# OPA4377__V2_0.net
KiCad netlist of a schematic drawn in EasyEDA Pro
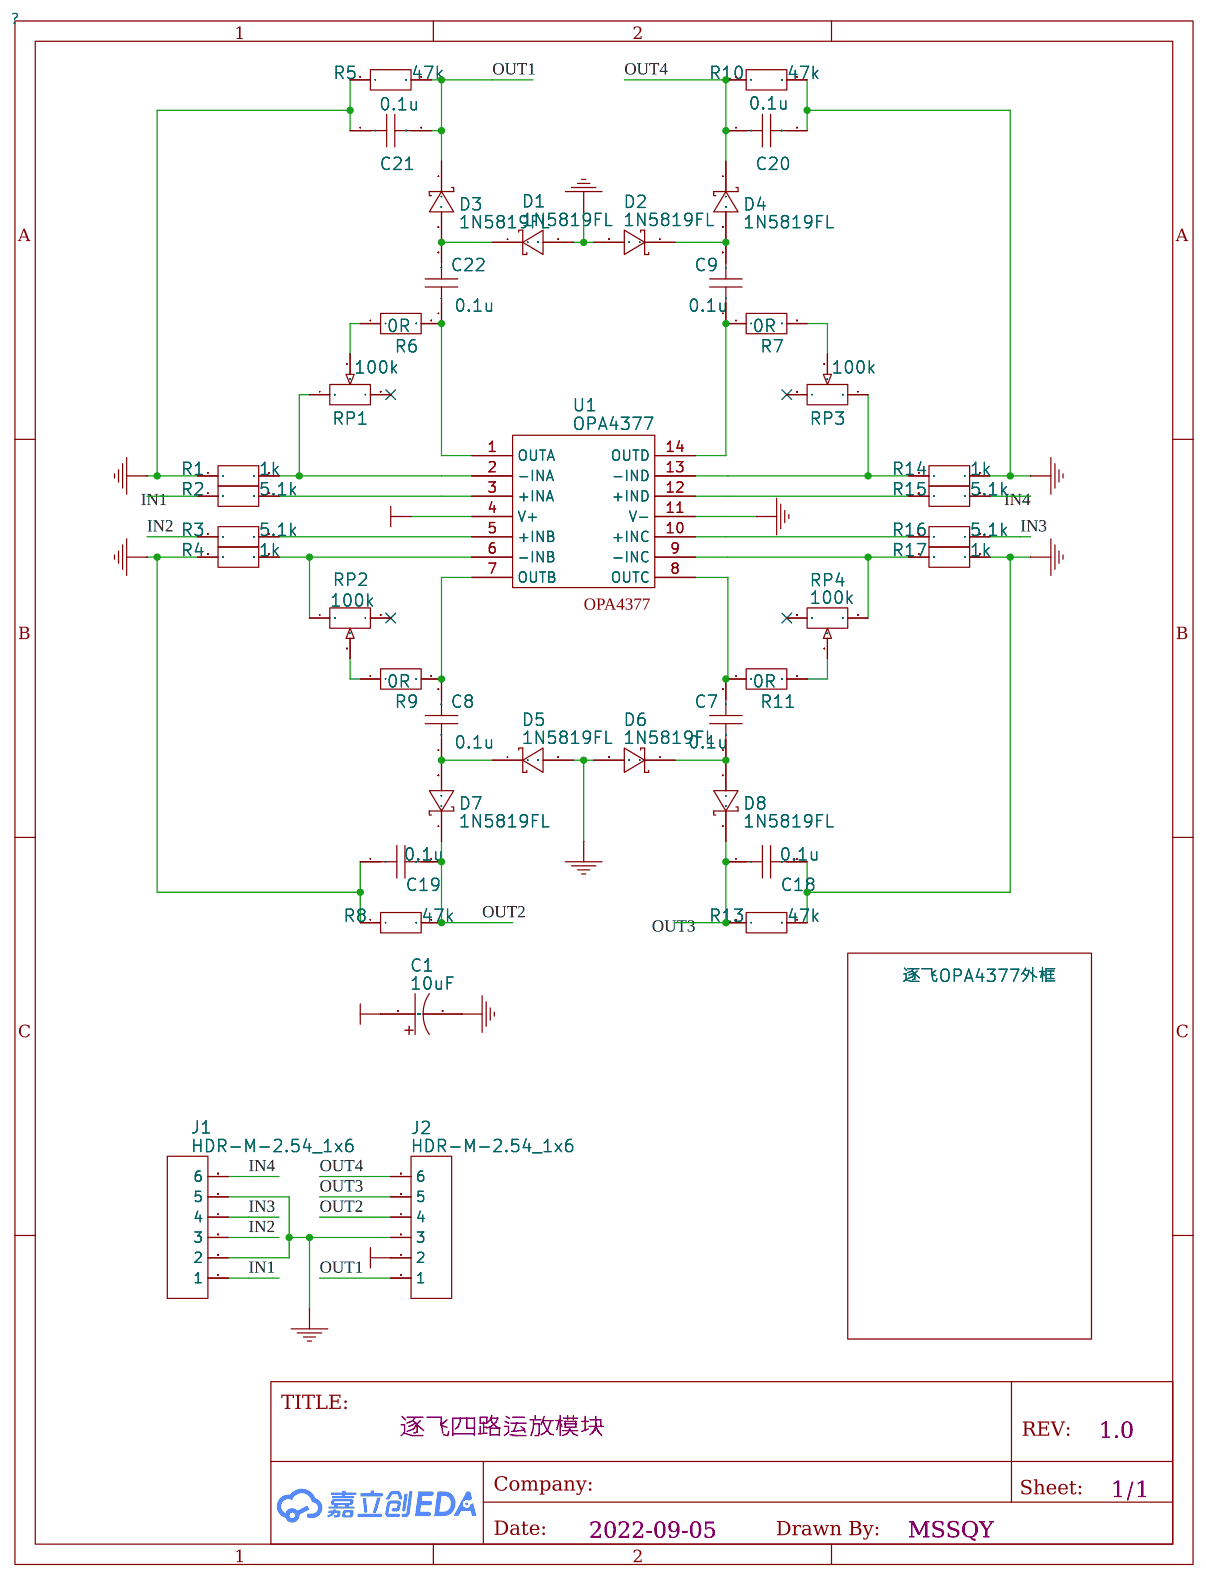
[diagram p0: schematic sheet]

(export (version "E")
  (design (tool "Eeschema 10.0.6"))
  (components
    (comp (ref "C1")
      (value "10uF")
      (fields (field (name "Manufacturer Part") "CA45-A-10V-10μF-K") (field (name "Manufacturer") "TORCH"))
      (libsource (lib "easyedapro") (part "10uF"))
    )
    (comp (ref "C7")
      (value "0.1u")
      (fields (field (name "Manufacturer Part") "MT18N101J500CT") (field (name "Manufacturer") "Huaxin S&T"))
      (libsource (lib "easyedapro") (part "0.1u"))
    )
    (comp (ref "C8")
      (value "0.1u")
      (fields (field (name "Manufacturer Part") "MT18N101J500CT") (field (name "Manufacturer") "Huaxin S&T"))
      (libsource (lib "easyedapro") (part "0.1u"))
    )
    (comp (ref "C9")
      (value "0.1u")
      (fields (field (name "Manufacturer Part") "MT18N101J500CT") (field (name "Manufacturer") "Huaxin S&T"))
      (libsource (lib "easyedapro") (part "0.1u"))
    )
    (comp (ref "C18")
      (value "0.1u")
      (fields (field (name "Manufacturer Part") "MT18N101J500CT") (field (name "Manufacturer") "Huaxin S&T"))
      (libsource (lib "easyedapro") (part "0.1u"))
    )
    (comp (ref "C19")
      (value "0.1u")
      (fields (field (name "Manufacturer Part") "MT18N101J500CT") (field (name "Manufacturer") "Huaxin S&T"))
      (libsource (lib "easyedapro") (part "0.1u"))
    )
    (comp (ref "C20")
      (value "0.1u")
      (fields (field (name "Manufacturer Part") "MT18N101J500CT") (field (name "Manufacturer") "Huaxin S&T"))
      (libsource (lib "easyedapro") (part "0.1u"))
    )
    (comp (ref "C21")
      (value "0.1u")
      (fields (field (name "Manufacturer Part") "MT18N101J500CT") (field (name "Manufacturer") "Huaxin S&T"))
      (libsource (lib "easyedapro") (part "0.1u"))
    )
    (comp (ref "C22")
      (value "0.1u")
      (fields (field (name "Manufacturer Part") "MT18N101J500CT") (field (name "Manufacturer") "Huaxin S&T"))
      (libsource (lib "easyedapro") (part "0.1u"))
    )
    (comp (ref "D1")
      (value "1N5819FL")
      (fields (field (name "Manufacturer") "KEXIN"))
      (libsource (lib "easyedapro") (part "1N5819FL"))
    )
    (comp (ref "D2")
      (value "1N5819FL")
      (fields (field (name "Manufacturer") "KEXIN"))
      (libsource (lib "easyedapro") (part "1N5819FL"))
    )
    (comp (ref "D3")
      (value "1N5819FL")
      (fields (field (name "Manufacturer") "KEXIN"))
      (libsource (lib "easyedapro") (part "1N5819FL"))
    )
    (comp (ref "D4")
      (value "1N5819FL")
      (fields (field (name "Manufacturer") "KEXIN"))
      (libsource (lib "easyedapro") (part "1N5819FL"))
    )
    (comp (ref "D5")
      (value "1N5819FL")
      (fields (field (name "Manufacturer") "KEXIN"))
      (libsource (lib "easyedapro") (part "1N5819FL"))
    )
    (comp (ref "D6")
      (value "1N5819FL")
      (fields (field (name "Manufacturer") "KEXIN"))
      (libsource (lib "easyedapro") (part "1N5819FL"))
    )
    (comp (ref "D7")
      (value "1N5819FL")
      (fields (field (name "Manufacturer") "KEXIN"))
      (libsource (lib "easyedapro") (part "1N5819FL"))
    )
    (comp (ref "D8")
      (value "1N5819FL")
      (fields (field (name "Manufacturer") "KEXIN"))
      (libsource (lib "easyedapro") (part "1N5819FL"))
    )
    (comp (ref "J1") (value "HDR-M-2.54_1x6") (libsource (lib "easyedapro") (part "HDR-M-2.54_1x6")))
    (comp (ref "J2") (value "HDR-M-2.54_1x6") (libsource (lib "") (part "HDR-M-2.54_1x6_1")))
    (comp (ref "R1")
      (value "1k")
      (fields (field (name "Manufacturer Part") "RT0603DRD071KL") (field (name "Manufacturer") "YAGEO"))
      (libsource (lib "easyedapro") (part "1k"))
    )
    (comp (ref "R2")
      (value "5.1k")
      (fields
        (field (name "Manufacturer Part") "RS-03K5101FT")
        (field (name "Manufacturer") "Guangdong Fenghua Advanced Tech")
      )
      (libsource (lib "easyedapro") (part "5.1k"))
    )
    (comp (ref "R3")
      (value "5.1k")
      (fields
        (field (name "Manufacturer Part") "RS-03K5101FT")
        (field (name "Manufacturer") "Guangdong Fenghua Advanced Tech")
      )
      (libsource (lib "easyedapro") (part "5.1k"))
    )
    (comp (ref "R4")
      (value "1k")
      (fields (field (name "Manufacturer Part") "RT0603DRD071KL") (field (name "Manufacturer") "YAGEO"))
      (libsource (lib "easyedapro") (part "1k"))
    )
    (comp (ref "R5")
      (value "47k")
      (fields (field (name "Manufacturer Part") "RS-03K473JT") (field (name "Manufacturer") "FH"))
      (libsource (lib "easyedapro") (part "0R"))
    )
    (comp (ref "R6")
      (value "0R")
      (fields (field (name "Manufacturer Part") "RS-03K473JT") (field (name "Manufacturer") "FH"))
      (libsource (lib "easyedapro") (part "0R"))
    )
    (comp (ref "R7")
      (value "0R")
      (fields (field (name "Manufacturer Part") "RS-03K473JT") (field (name "Manufacturer") "FH"))
      (libsource (lib "easyedapro") (part "0R"))
    )
    (comp (ref "R8")
      (value "47k")
      (fields (field (name "Manufacturer Part") "RS-03K473JT") (field (name "Manufacturer") "FH"))
      (libsource (lib "easyedapro") (part "0R"))
    )
    (comp (ref "R9")
      (value "0R")
      (fields (field (name "Manufacturer Part") "RS-03K473JT") (field (name "Manufacturer") "FH"))
      (libsource (lib "easyedapro") (part "0R"))
    )
    (comp (ref "R10")
      (value "47k")
      (fields (field (name "Manufacturer Part") "RS-03K473JT") (field (name "Manufacturer") "FH"))
      (libsource (lib "easyedapro") (part "0R"))
    )
    (comp (ref "R11")
      (value "0R")
      (fields (field (name "Manufacturer Part") "RS-03K473JT") (field (name "Manufacturer") "FH"))
      (libsource (lib "easyedapro") (part "0R"))
    )
    (comp (ref "R13")
      (value "47k")
      (fields (field (name "Manufacturer Part") "RS-03K473JT") (field (name "Manufacturer") "FH"))
      (libsource (lib "easyedapro") (part "0R"))
    )
    (comp (ref "R14")
      (value "1k")
      (fields (field (name "Manufacturer Part") "RT0603DRD071KL") (field (name "Manufacturer") "YAGEO"))
      (libsource (lib "easyedapro") (part "1k"))
    )
    (comp (ref "R15")
      (value "5.1k")
      (fields
        (field (name "Manufacturer Part") "RS-03K5101FT")
        (field (name "Manufacturer") "Guangdong Fenghua Advanced Tech")
      )
      (libsource (lib "easyedapro") (part "5.1k"))
    )
    (comp (ref "R16")
      (value "5.1k")
      (fields
        (field (name "Manufacturer Part") "RS-03K5101FT")
        (field (name "Manufacturer") "Guangdong Fenghua Advanced Tech")
      )
      (libsource (lib "easyedapro") (part "5.1k"))
    )
    (comp (ref "R17")
      (value "1k")
      (fields (field (name "Manufacturer Part") "RT0603DRD071KL") (field (name "Manufacturer") "YAGEO"))
      (libsource (lib "easyedapro") (part "1k"))
    )
    (comp (ref "RP1")
      (value "100k")
      (fields (field (name "Manufacturer") "Nidec Copal Elec"))
      (libsource (lib "") (part "100k_2"))
    )
    (comp (ref "RP2")
      (value "100k")
      (fields (field (name "Manufacturer") "Nidec Copal Elec"))
      (libsource (lib "") (part "100k_1"))
    )
    (comp (ref "RP3")
      (value "100k")
      (fields (field (name "Manufacturer") "Nidec Copal Elec"))
      (libsource (lib "") (part "100k_1"))
    )
    (comp (ref "RP4")
      (value "100k")
      (fields (field (name "Manufacturer") "Nidec Copal Elec"))
      (libsource (lib "easyedapro") (part "100k"))
    )
    (comp (ref "U1")
      (value "OPA4377")
      (fields (field (name "Manufacturer") "OPA4377AIPWR"))
      (libsource (lib "easyedapro") (part "OPA4377"))
    )
    (comp (ref "U2") (value "逐飞OPA4377外框") (libsource (lib "easyedapro") (part "逐飞OPA4377外框")))
  )
  (nets
    (net (code "1") (name "/IN1") (class "Default")
      (node (ref "J1") (pin "1") (pinfunction "1_1") (pintype "input"))
      (node (ref "R2") (pin "1") (pinfunction "1_1") (pintype "input"))
    )
    (net (code "2") (name "/IN2") (class "Default")
      (node (ref "J1") (pin "3") (pinfunction "3_3") (pintype "input"))
      (node (ref "R3") (pin "1") (pinfunction "1_1") (pintype "input"))
    )
    (net (code "3") (name "/IN3") (class "Default")
      (node (ref "J1") (pin "4") (pinfunction "4_4") (pintype "input"))
      (node (ref "R16") (pin "2") (pinfunction "2_2") (pintype "input"))
    )
    (net (code "4") (name "/IN4") (class "Default")
      (node (ref "J1") (pin "6") (pinfunction "6_6") (pintype "input"))
      (node (ref "R15") (pin "2") (pinfunction "2_2") (pintype "input"))
    )
    (net (code "5") (name "/OUT1") (class "Default")
      (node (ref "C21") (pin "2") (pinfunction "2_2") (pintype "input"))
      (node (ref "D3") (pin "1") (pinfunction "1_1") (pintype "input"))
      (node (ref "J2") (pin "1") (pinfunction "1_1") (pintype "input"))
      (node (ref "R5") (pin "2") (pinfunction "2_2") (pintype "input"))
    )
    (net (code "6") (name "/OUT2") (class "Default")
      (node (ref "C19") (pin "2") (pinfunction "2_2") (pintype "input"))
      (node (ref "D7") (pin "1") (pinfunction "1_1") (pintype "input"))
      (node (ref "J2") (pin "4") (pinfunction "4_4") (pintype "input"))
      (node (ref "R8") (pin "2") (pinfunction "2_2") (pintype "input"))
    )
    (net (code "7") (name "/OUT3") (class "Default")
      (node (ref "C18") (pin "1") (pinfunction "1_1") (pintype "input"))
      (node (ref "D8") (pin "1") (pinfunction "1_1") (pintype "input"))
      (node (ref "J2") (pin "5") (pinfunction "5_5") (pintype "input"))
      (node (ref "R13") (pin "1") (pinfunction "1_1") (pintype "input"))
    )
    (net (code "8") (name "/OUT4") (class "Default")
      (node (ref "C20") (pin "1") (pinfunction "1_1") (pintype "input"))
      (node (ref "D4") (pin "1") (pinfunction "1_1") (pintype "input"))
      (node (ref "J2") (pin "6") (pinfunction "6_6") (pintype "input"))
      (node (ref "R10") (pin "1") (pinfunction "1_1") (pintype "input"))
    )
    (net (code "9") (name "GND") (class "Default")
      (node (ref "C1") (pin "2") (pinfunction "2_2") (pintype "input"))
      (node (ref "C18") (pin "2") (pinfunction "2_2") (pintype "input"))
      (node (ref "C19") (pin "1") (pinfunction "1_1") (pintype "input"))
      (node (ref "C20") (pin "2") (pinfunction "2_2") (pintype "input"))
      (node (ref "C21") (pin "1") (pinfunction "1_1") (pintype "input"))
      (node (ref "D1") (pin "2") (pinfunction "2_2") (pintype "input"))
      (node (ref "D2") (pin "2") (pinfunction "2_2") (pintype "input"))
      (node (ref "D5") (pin "2") (pinfunction "2_2") (pintype "input"))
      (node (ref "D6") (pin "2") (pinfunction "2_2") (pintype "input"))
      (node (ref "J1") (pin "2") (pinfunction "2_2") (pintype "input"))
      (node (ref "J1") (pin "5") (pinfunction "5_5") (pintype "input"))
      (node (ref "J2") (pin "3") (pinfunction "3_3") (pintype "input"))
      (node (ref "R1") (pin "1") (pinfunction "1_1") (pintype "input"))
      (node (ref "R10") (pin "2") (pinfunction "2_2") (pintype "input"))
      (node (ref "R13") (pin "2") (pinfunction "2_2") (pintype "input"))
      (node (ref "R14") (pin "2") (pinfunction "2_2") (pintype "input"))
      (node (ref "R17") (pin "2") (pinfunction "2_2") (pintype "input"))
      (node (ref "R4") (pin "1") (pinfunction "1_1") (pintype "input"))
      (node (ref "R5") (pin "1") (pinfunction "1_1") (pintype "input"))
      (node (ref "R8") (pin "1") (pinfunction "1_1") (pintype "input"))
      (node (ref "U1") (pin "11") (pinfunction "V-_11") (pintype "input"))
    )
    (net (code "10") (name "Net-(C7-Pad1)") (class "Default")
      (node (ref "C7") (pin "1") (pinfunction "1_1") (pintype "input"))
      (node (ref "D6") (pin "1") (pinfunction "1_1") (pintype "input"))
      (node (ref "D8") (pin "2") (pinfunction "2_2") (pintype "input"))
    )
    (net (code "11") (name "Net-(C8-Pad1)") (class "Default")
      (node (ref "C8") (pin "1") (pinfunction "1_1") (pintype "input"))
      (node (ref "D5") (pin "1") (pinfunction "1_1") (pintype "input"))
      (node (ref "D7") (pin "2") (pinfunction "2_2") (pintype "input"))
    )
    (net (code "12") (name "Net-(C9-Pad2)") (class "Default")
      (node (ref "C9") (pin "2") (pinfunction "2_2") (pintype "input"))
      (node (ref "D2") (pin "1") (pinfunction "1_1") (pintype "input"))
      (node (ref "D4") (pin "2") (pinfunction "2_2") (pintype "input"))
    )
    (net (code "13") (name "Net-(C22-Pad2)") (class "Default")
      (node (ref "C22") (pin "2") (pinfunction "2_2") (pintype "input"))
      (node (ref "D1") (pin "1") (pinfunction "1_1") (pintype "input"))
      (node (ref "D3") (pin "2") (pinfunction "2_2") (pintype "input"))
    )
    (net (code "14") (name "Net-(R6-Pad1)") (class "Default")
      (node (ref "R6") (pin "1") (pinfunction "1_1") (pintype "input"))
      (node (ref "RP1") (pin "2") (pinfunction "2_2") (pintype "input"))
    )
    (net (code "15") (name "Net-(R7-Pad2)") (class "Default")
      (node (ref "R7") (pin "2") (pinfunction "2_2") (pintype "input"))
      (node (ref "RP3") (pin "2") (pinfunction "2_2") (pintype "input"))
    )
    (net (code "16") (name "Net-(R9-Pad1)") (class "Default")
      (node (ref "R9") (pin "1") (pinfunction "1_1") (pintype "input"))
      (node (ref "RP2") (pin "2") (pinfunction "2_2") (pintype "input"))
    )
    (net (code "17") (name "Net-(R11-Pad2)") (class "Default")
      (node (ref "R11") (pin "2") (pinfunction "2_2") (pintype "input"))
      (node (ref "RP4") (pin "2") (pinfunction "2_2") (pintype "input"))
    )
    (net (code "18") (name "Net-(RP1-3)") (class "Default")
      (node (ref "R1") (pin "2") (pinfunction "2_2") (pintype "input"))
      (node (ref "RP1") (pin "1") (pinfunction "3_1") (pintype "input"))
      (node (ref "U1") (pin "2") (pinfunction "-INA_2") (pintype "input"))
    )
    (net (code "19") (name "Net-(RP2-3)") (class "Default")
      (node (ref "R4") (pin "2") (pinfunction "2_2") (pintype "input"))
      (node (ref "RP2") (pin "1") (pinfunction "3_1") (pintype "input"))
      (node (ref "U1") (pin "6") (pinfunction "-INB_6") (pintype "input"))
    )
    (net (code "20") (name "Net-(RP3-3)") (class "Default")
      (node (ref "R14") (pin "1") (pinfunction "1_1") (pintype "input"))
      (node (ref "RP3") (pin "1") (pinfunction "3_1") (pintype "input"))
      (node (ref "U1") (pin "13") (pinfunction "-IND_13") (pintype "input"))
    )
    (net (code "21") (name "Net-(U1-+INA)") (class "Default")
      (node (ref "R2") (pin "2") (pinfunction "2_2") (pintype "input"))
      (node (ref "U1") (pin "3") (pinfunction "+INA_3") (pintype "input"))
    )
    (net (code "22") (name "Net-(U1-+INB)") (class "Default")
      (node (ref "R3") (pin "2") (pinfunction "2_2") (pintype "input"))
      (node (ref "U1") (pin "5") (pinfunction "+INB_5") (pintype "input"))
    )
    (net (code "23") (name "Net-(U1-+INC)") (class "Default")
      (node (ref "R16") (pin "1") (pinfunction "1_1") (pintype "input"))
      (node (ref "U1") (pin "10") (pinfunction "+INC_10") (pintype "input"))
    )
    (net (code "24") (name "Net-(U1-+IND)") (class "Default")
      (node (ref "R15") (pin "1") (pinfunction "1_1") (pintype "input"))
      (node (ref "U1") (pin "12") (pinfunction "+IND_12") (pintype "input"))
    )
    (net (code "25") (name "Net-(U1--INC)") (class "Default")
      (node (ref "R17") (pin "1") (pinfunction "1_1") (pintype "input"))
      (node (ref "RP4") (pin "1") (pinfunction "1_1") (pintype "input"))
      (node (ref "U1") (pin "9") (pinfunction "-INC_9") (pintype "input"))
    )
    (net (code "26") (name "Net-(U1-OUTA)") (class "Default")
      (node (ref "C22") (pin "1") (pinfunction "1_1") (pintype "input"))
      (node (ref "R6") (pin "2") (pinfunction "2_2") (pintype "input"))
      (node (ref "U1") (pin "1") (pinfunction "OUTA_1") (pintype "input"))
    )
    (net (code "27") (name "Net-(U1-OUTB)") (class "Default")
      (node (ref "C8") (pin "2") (pinfunction "2_2") (pintype "input"))
      (node (ref "R9") (pin "2") (pinfunction "2_2") (pintype "input"))
      (node (ref "U1") (pin "7") (pinfunction "OUTB_7") (pintype "input"))
    )
    (net (code "28") (name "Net-(U1-OUTC)") (class "Default")
      (node (ref "C7") (pin "2") (pinfunction "2_2") (pintype "input"))
      (node (ref "R11") (pin "1") (pinfunction "1_1") (pintype "input"))
      (node (ref "U1") (pin "8") (pinfunction "OUTC_8") (pintype "input"))
    )
    (net (code "29") (name "Net-(U1-OUTD)") (class "Default")
      (node (ref "C9") (pin "1") (pinfunction "1_1") (pintype "input"))
      (node (ref "R7") (pin "1") (pinfunction "1_1") (pintype "input"))
      (node (ref "U1") (pin "14") (pinfunction "OUTD_14") (pintype "input"))
    )
    (net (code "30") (name "VCC") (class "Default")
      (node (ref "C1") (pin "1") (pinfunction "1_1") (pintype "input"))
      (node (ref "J2") (pin "2") (pinfunction "2_2") (pintype "input"))
      (node (ref "U1") (pin "4") (pinfunction "V+_4") (pintype "input"))
    )
    (net (code "31") (name "unconnected-(RP1-1-Pad3)") (class "Default")
      (node (ref "RP1") (pin "3") (pinfunction "1_3") (pintype "input+no_connect"))
    )
    (net (code "32") (name "unconnected-(RP2-1-Pad3)") (class "Default")
      (node (ref "RP2") (pin "3") (pinfunction "1_3") (pintype "input+no_connect"))
    )
    (net (code "33") (name "unconnected-(RP3-1-Pad3)") (class "Default")
      (node (ref "RP3") (pin "3") (pinfunction "1_3") (pintype "input+no_connect"))
    )
    (net (code "34") (name "unconnected-(RP4-Pad3)") (class "Default")
      (node (ref "RP4") (pin "3") (pinfunction "3_3") (pintype "input+no_connect"))
    )
  )
)
